# Hbridge0.net
KiCad netlist of a schematic drawn in Altium Designer
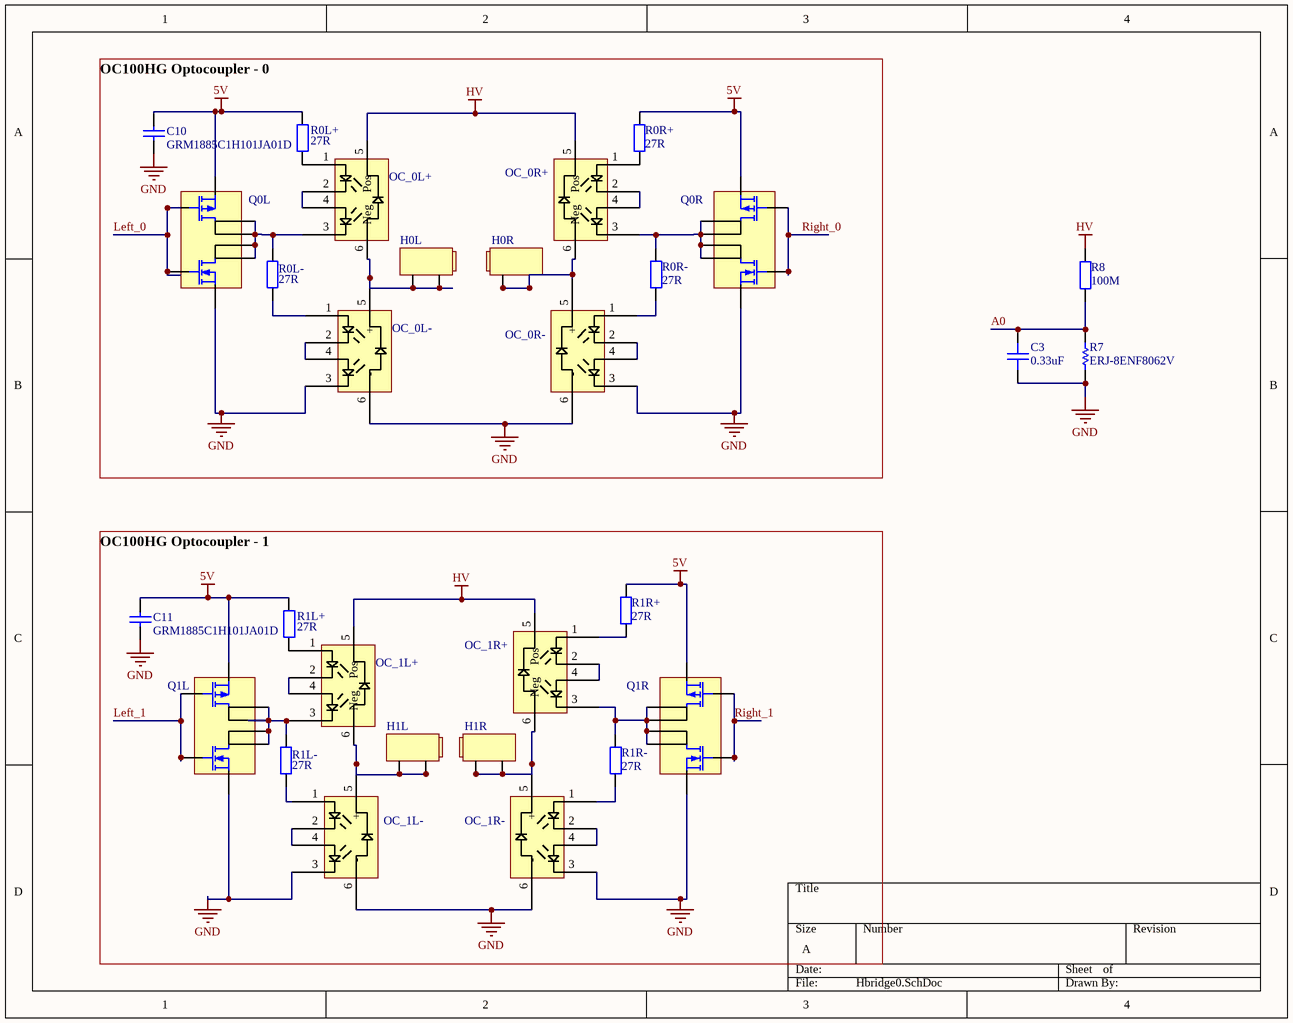
[diagram p0: Hbridge0.SchDoc]

(export (version "E")
  (design (tool "Eeschema 10.0.6"))
  (components
    (comp (ref "C3")
      (value "0.33uF")
      (footprint "1206 CAP")
      (description "‎399-1285-1-ND‎ Manufacturer: ‎C1206C334K3RACTU‎")
      (fields (field (name "Comment") "Capacitor 0.33uF"))
      (libsource (lib "Schlib") (part "Capacitor 0.33uF"))
    )
    (comp (ref "C10")
      (value "GRM1885C1H101JA01D")
      (footprint "CAPC1608X90X35NL10T15")
      (fields (field (name "MANUFACTURER") "Murata"))
      (libsource (lib "Altium Content Vault") (part "CAP"))
    )
    (comp (ref "C11")
      (value "GRM1885C1H101JA01D")
      (footprint "CAPC1608X90X35NL10T15")
      (fields (field (name "MANUFACTURER") "Murata"))
      (libsource (lib "Altium Content Vault") (part "CAP"))
    )
    (comp (ref "H0L")
      (value "HV Socket")
      (footprint "HV Socket 2mm")
      (description "Black: 486-3654-ND\r\nRed: ‎486-3655-ND‎")
      (libsource (lib "") (part "HV Socket_1"))
    )
    (comp (ref "H0R")
      (value "HV Socket")
      (footprint "HV Socket 2mm")
      (description "Black: 486-3654-ND\r\nRed: ‎486-3655-ND‎")
      (libsource (lib "Schlib") (part "HV Socket"))
    )
    (comp (ref "H1L")
      (value "HV Socket")
      (footprint "HV Socket 2mm")
      (description "Black: 486-3654-ND\r\nRed: ‎486-3655-ND‎")
      (libsource (lib "") (part "HV Socket_1"))
    )
    (comp (ref "H1R")
      (value "HV Socket")
      (footprint "HV Socket 2mm")
      (description "Black: 486-3654-ND\r\nRed: ‎486-3655-ND‎")
      (libsource (lib "Schlib") (part "HV Socket"))
    )
    (comp (ref "OC_0L+") (value "OC100HG") (footprint "OC100G") (libsource (lib "") (part "OC100HG_1")))
    (comp (ref "OC_0L-") (value "OC100HG") (footprint "OC100G") (libsource (lib "") (part "OC100HG_3")))
    (comp (ref "OC_0R+") (value "OC100HG") (footprint "OC100G") (libsource (lib "") (part "OC100HG_2")))
    (comp (ref "OC_0R-") (value "OC100HG") (footprint "OC100G") (libsource (lib "Schlib1") (part "OC100HG")))
    (comp (ref "OC_1L+") (value "OC100HG") (footprint "OC100G") (libsource (lib "") (part "OC100HG_1")))
    (comp (ref "OC_1L-") (value "OC100HG") (footprint "OC100G") (libsource (lib "") (part "OC100HG_3")))
    (comp (ref "OC_1R+") (value "OC100HG") (footprint "OC100G") (libsource (lib "") (part "OC100HG_2")))
    (comp (ref "OC_1R-") (value "OC100HG") (footprint "OC100G") (libsource (lib "Schlib1") (part "OC100HG")))
    (comp (ref "Q0L")
      (value "Dual MOSFET")
      (footprint "SO-8")
      (libsource (lib "Schlib") (part "Dual MOSFET"))
    )
    (comp (ref "Q0R") (value "Dual MOSFET") (footprint "SO-8") (libsource (lib "") (part "Dual MOSFET_1")))
    (comp (ref "Q1L")
      (value "Dual MOSFET")
      (footprint "SO-8")
      (libsource (lib "Schlib") (part "Dual MOSFET"))
    )
    (comp (ref "Q1R") (value "Dual MOSFET") (footprint "SO-8") (libsource (lib "") (part "Dual MOSFET_1")))
    (comp (ref "R0L+")
      (value "27R")
      (footprint "1206 R")
      (description "Manufacturer ‎HRG3216Q-27R0-D-T1‎\r\nDigikey ‎408-1908-1-ND")
      (fields (field (name "Comment") "Resistor"))
      (libsource (lib "") (part "Resistor 27R_2"))
    )
    (comp (ref "R0L-")
      (value "27R")
      (footprint "1206 R")
      (description "Manufacturer ‎HRG3216Q-27R0-D-T1‎\r\nDigikey ‎408-1908-1-ND")
      (fields (field (name "Comment") "Resistor"))
      (libsource (lib "") (part "Resistor 27R_1"))
    )
    (comp (ref "R0R+")
      (value "27R")
      (footprint "1206 R")
      (description "Manufacturer ‎HRG3216Q-27R0-D-T1‎\r\nDigikey ‎408-1908-1-ND")
      (fields (field (name "Comment") "Resistor"))
      (libsource (lib "Schlib") (part "Resistor 27R"))
    )
    (comp (ref "R0R-")
      (value "27R")
      (footprint "1206 R")
      (description "Manufacturer ‎HRG3216Q-27R0-D-T1‎\r\nDigikey ‎408-1908-1-ND")
      (fields (field (name "Comment") "Resistor"))
      (libsource (lib "") (part "Resistor 27R_3"))
    )
    (comp (ref "R1L+")
      (value "27R")
      (footprint "1206 R")
      (description "Manufacturer ‎HRG3216Q-27R0-D-T1‎\r\nDigikey ‎408-1908-1-ND")
      (fields (field (name "Comment") "Resistor"))
      (libsource (lib "") (part "Resistor 27R_2"))
    )
    (comp (ref "R1L-")
      (value "27R")
      (footprint "1206 R")
      (description "Manufacturer ‎HRG3216Q-27R0-D-T1‎\r\nDigikey ‎408-1908-1-ND")
      (fields (field (name "Comment") "Resistor"))
      (libsource (lib "") (part "Resistor 27R_1"))
    )
    (comp (ref "R1R+")
      (value "27R")
      (footprint "1206 R")
      (description "Manufacturer ‎HRG3216Q-27R0-D-T1‎\r\nDigikey ‎408-1908-1-ND")
      (fields (field (name "Comment") "Resistor"))
      (libsource (lib "Schlib") (part "Resistor 27R"))
    )
    (comp (ref "R1R-")
      (value "27R")
      (footprint "1206 R")
      (description "Manufacturer ‎HRG3216Q-27R0-D-T1‎\r\nDigikey ‎408-1908-1-ND")
      (fields (field (name "Comment") "Resistor"))
      (libsource (lib "") (part "Resistor 27R_3"))
    )
    (comp (ref "R7")
      (value "ERJ-8ENF8062V")
      (footprint "RESC3216X70X50LL05T20")
      (fields (field (name "MANUFACTURER") "Panasonic"))
      (libsource (lib "Altium Content Vault") (part "RES"))
    )
    (comp (ref "R8")
      (value "100M")
      (footprint "HV resistor")
      (description "Digikey:‎SM102031006FE-ND‎\r\nManufacturer: ‎SM102031006FE-ND‎")
      (fields (field (name "Comment") "Resistor"))
      (libsource (lib "Schlib") (part "Resistor 100M"))
    )
  )
  (nets
    (net (code "1") (name "/A0") (class "Default")
      (node (ref "C3") (pin "2") (pinfunction "2_2") (pintype "passive"))
      (node (ref "R7") (pin "2") (pinfunction "2_2") (pintype "passive"))
      (node (ref "R8") (pin "1") (pinfunction "1_1") (pintype "passive"))
    )
    (net (code "2") (name "/Left_0") (class "Default")
      (node (ref "Q0L") (pin "2") (pinfunction "2_2") (pintype "passive"))
      (node (ref "Q0L") (pin "4") (pinfunction "4_4") (pintype "passive"))
    )
    (net (code "3") (name "/Left_1") (class "Default")
      (node (ref "Q1L") (pin "2") (pinfunction "2_2") (pintype "passive"))
      (node (ref "Q1L") (pin "4") (pinfunction "4_4") (pintype "passive"))
    )
    (net (code "4") (name "/Right_0") (class "Default")
      (node (ref "Q0R") (pin "2") (pinfunction "2_2") (pintype "passive"))
      (node (ref "Q0R") (pin "4") (pinfunction "4_4") (pintype "passive"))
    )
    (net (code "5") (name "/Right_1") (class "Default")
      (node (ref "Q1R") (pin "2") (pinfunction "2_2") (pintype "passive"))
      (node (ref "Q1R") (pin "4") (pinfunction "4_4") (pintype "passive"))
    )
    (net (code "6") (name "5V") (class "Default")
      (node (ref "C10") (pin "2") (pinfunction "2_2") (pintype "passive"))
      (node (ref "C11") (pin "2") (pinfunction "2_2") (pintype "passive"))
      (node (ref "Q0L") (pin "3") (pinfunction "3_3") (pintype "passive"))
      (node (ref "Q0R") (pin "3") (pinfunction "3_3") (pintype "passive"))
      (node (ref "Q1L") (pin "3") (pinfunction "3_3") (pintype "passive"))
      (node (ref "Q1R") (pin "3") (pinfunction "3_3") (pintype "passive"))
      (node (ref "R0L+") (pin "2") (pinfunction "2_2") (pintype "passive"))
      (node (ref "R0R+") (pin "2") (pinfunction "2_2") (pintype "passive"))
      (node (ref "R1L+") (pin "2") (pinfunction "2_2") (pintype "passive"))
      (node (ref "R1R+") (pin "2") (pinfunction "2_2") (pintype "passive"))
    )
    (net (code "7") (name "GND") (class "Default")
      (node (ref "C10") (pin "1") (pinfunction "1_1") (pintype "passive"))
      (node (ref "C11") (pin "1") (pinfunction "1_1") (pintype "passive"))
      (node (ref "C3") (pin "1") (pinfunction "1_1") (pintype "passive"))
      (node (ref "OC_0L-") (pin "3") (pinfunction "LED_2-_3") (pintype "passive"))
      (node (ref "OC_0L-") (pin "6") (pinfunction "-_6") (pintype "passive"))
      (node (ref "OC_0R-") (pin "3") (pinfunction "LED_2-_3") (pintype "passive"))
      (node (ref "OC_0R-") (pin "6") (pinfunction "-_6") (pintype "passive"))
      (node (ref "OC_1L-") (pin "3") (pinfunction "LED_2-_3") (pintype "passive"))
      (node (ref "OC_1L-") (pin "6") (pinfunction "-_6") (pintype "passive"))
      (node (ref "OC_1R-") (pin "3") (pinfunction "LED_2-_3") (pintype "passive"))
      (node (ref "OC_1R-") (pin "6") (pinfunction "-_6") (pintype "passive"))
      (node (ref "Q0L") (pin "1") (pinfunction "1_1") (pintype "passive"))
      (node (ref "Q0R") (pin "1") (pinfunction "1_1") (pintype "passive"))
      (node (ref "Q1L") (pin "1") (pinfunction "1_1") (pintype "passive"))
      (node (ref "Q1R") (pin "1") (pinfunction "1_1") (pintype "passive"))
      (node (ref "R7") (pin "1") (pinfunction "1_1") (pintype "passive"))
    )
    (net (code "8") (name "HV") (class "Default")
      (node (ref "OC_0L+") (pin "5") (pinfunction "Pos_5") (pintype "passive"))
      (node (ref "OC_0R+") (pin "5") (pinfunction "Pos_5") (pintype "passive"))
      (node (ref "OC_1L+") (pin "5") (pinfunction "Pos_5") (pintype "passive"))
      (node (ref "OC_1R+") (pin "5") (pinfunction "Pos_5") (pintype "passive"))
      (node (ref "R8") (pin "2") (pinfunction "2_2") (pintype "passive"))
    )
    (net (code "9") (name "Net-(OC_0L+-LED_1+)") (class "Default")
      (node (ref "OC_0L+") (pin "1") (pinfunction "LED_1+_1") (pintype "passive"))
      (node (ref "R0L+") (pin "1") (pinfunction "1_1") (pintype "passive"))
    )
    (net (code "10") (name "Net-(OC_0L+-LED_1-)") (class "Default")
      (node (ref "OC_0L+") (pin "2") (pinfunction "LED_1-_2") (pintype "passive"))
      (node (ref "OC_0L+") (pin "4") (pinfunction "LED_2+_4") (pintype "passive"))
    )
    (net (code "11") (name "Net-(OC_0L+-LED_2-)") (class "Default")
      (node (ref "OC_0L+") (pin "3") (pinfunction "LED_2-_3") (pintype "passive"))
      (node (ref "Q0L") (pin "5") (pinfunction "5_5") (pintype "passive"))
      (node (ref "Q0L") (pin "6") (pinfunction "6_6") (pintype "passive"))
      (node (ref "Q0L") (pin "7") (pinfunction "7_7") (pintype "passive"))
      (node (ref "Q0L") (pin "8") (pinfunction "8_8") (pintype "passive"))
      (node (ref "R0L-") (pin "1") (pinfunction "1_1") (pintype "passive"))
    )
    (net (code "12") (name "Net-(OC_0L+-Neg)") (class "Default")
      (node (ref "H0L") (pin "1") (pinfunction "1_1") (pintype "passive"))
      (node (ref "H0L") (pin "2") (pinfunction "2_2") (pintype "passive"))
      (node (ref "OC_0L+") (pin "6") (pinfunction "Neg_6") (pintype "passive"))
      (node (ref "OC_0L-") (pin "5") (pinfunction "+_5") (pintype "passive"))
    )
    (net (code "13") (name "Net-(OC_0L--LED_1+)") (class "Default")
      (node (ref "OC_0L-") (pin "1") (pinfunction "LED_1+_1") (pintype "passive"))
      (node (ref "R0L-") (pin "2") (pinfunction "2_2") (pintype "passive"))
    )
    (net (code "14") (name "Net-(OC_0L--LED_1-)") (class "Default")
      (node (ref "OC_0L-") (pin "2") (pinfunction "LED_1-_2") (pintype "passive"))
      (node (ref "OC_0L-") (pin "4") (pinfunction "LED_2+_4") (pintype "passive"))
    )
    (net (code "15") (name "Net-(OC_0R+-LED_1+)") (class "Default")
      (node (ref "OC_0R+") (pin "1") (pinfunction "LED_1+_1") (pintype "passive"))
      (node (ref "R0R+") (pin "1") (pinfunction "1_1") (pintype "passive"))
    )
    (net (code "16") (name "Net-(OC_0R+-LED_1-)") (class "Default")
      (node (ref "OC_0R+") (pin "2") (pinfunction "LED_1-_2") (pintype "passive"))
      (node (ref "OC_0R+") (pin "4") (pinfunction "LED_2+_4") (pintype "passive"))
    )
    (net (code "17") (name "Net-(OC_0R+-LED_2-)") (class "Default")
      (node (ref "OC_0R+") (pin "3") (pinfunction "LED_2-_3") (pintype "passive"))
      (node (ref "Q0R") (pin "5") (pinfunction "5_5") (pintype "passive"))
      (node (ref "Q0R") (pin "6") (pinfunction "6_6") (pintype "passive"))
      (node (ref "Q0R") (pin "7") (pinfunction "7_7") (pintype "passive"))
      (node (ref "Q0R") (pin "8") (pinfunction "8_8") (pintype "passive"))
      (node (ref "R0R-") (pin "1") (pinfunction "1_1") (pintype "passive"))
    )
    (net (code "18") (name "Net-(OC_0R+-Neg)") (class "Default")
      (node (ref "H0R") (pin "1") (pinfunction "1_1") (pintype "passive"))
      (node (ref "H0R") (pin "2") (pinfunction "2_2") (pintype "passive"))
      (node (ref "OC_0R+") (pin "6") (pinfunction "Neg_6") (pintype "passive"))
      (node (ref "OC_0R-") (pin "5") (pinfunction "+_5") (pintype "passive"))
    )
    (net (code "19") (name "Net-(OC_0R--LED_1+)") (class "Default")
      (node (ref "OC_0R-") (pin "1") (pinfunction "LED_1+_1") (pintype "passive"))
      (node (ref "R0R-") (pin "2") (pinfunction "2_2") (pintype "passive"))
    )
    (net (code "20") (name "Net-(OC_0R--LED_1-)") (class "Default")
      (node (ref "OC_0R-") (pin "2") (pinfunction "LED_1-_2") (pintype "passive"))
      (node (ref "OC_0R-") (pin "4") (pinfunction "LED_2+_4") (pintype "passive"))
    )
    (net (code "21") (name "Net-(OC_1L+-LED_1+)") (class "Default")
      (node (ref "OC_1L+") (pin "1") (pinfunction "LED_1+_1") (pintype "passive"))
      (node (ref "R1L+") (pin "1") (pinfunction "1_1") (pintype "passive"))
    )
    (net (code "22") (name "Net-(OC_1L+-LED_1-)") (class "Default")
      (node (ref "OC_1L+") (pin "2") (pinfunction "LED_1-_2") (pintype "passive"))
      (node (ref "OC_1L+") (pin "4") (pinfunction "LED_2+_4") (pintype "passive"))
    )
    (net (code "23") (name "Net-(OC_1L+-LED_2-)") (class "Default")
      (node (ref "OC_1L+") (pin "3") (pinfunction "LED_2-_3") (pintype "passive"))
      (node (ref "Q1L") (pin "5") (pinfunction "5_5") (pintype "passive"))
      (node (ref "Q1L") (pin "6") (pinfunction "6_6") (pintype "passive"))
      (node (ref "Q1L") (pin "7") (pinfunction "7_7") (pintype "passive"))
      (node (ref "Q1L") (pin "8") (pinfunction "8_8") (pintype "passive"))
      (node (ref "R1L-") (pin "1") (pinfunction "1_1") (pintype "passive"))
    )
    (net (code "24") (name "Net-(OC_1L+-Neg)") (class "Default")
      (node (ref "H1L") (pin "1") (pinfunction "1_1") (pintype "passive"))
      (node (ref "H1L") (pin "2") (pinfunction "2_2") (pintype "passive"))
      (node (ref "OC_1L+") (pin "6") (pinfunction "Neg_6") (pintype "passive"))
      (node (ref "OC_1L-") (pin "5") (pinfunction "+_5") (pintype "passive"))
    )
    (net (code "25") (name "Net-(OC_1L--LED_1+)") (class "Default")
      (node (ref "OC_1L-") (pin "1") (pinfunction "LED_1+_1") (pintype "passive"))
      (node (ref "R1L-") (pin "2") (pinfunction "2_2") (pintype "passive"))
    )
    (net (code "26") (name "Net-(OC_1L--LED_1-)") (class "Default")
      (node (ref "OC_1L-") (pin "2") (pinfunction "LED_1-_2") (pintype "passive"))
      (node (ref "OC_1L-") (pin "4") (pinfunction "LED_2+_4") (pintype "passive"))
    )
    (net (code "27") (name "Net-(OC_1R+-LED_1+)") (class "Default")
      (node (ref "OC_1R+") (pin "1") (pinfunction "LED_1+_1") (pintype "passive"))
      (node (ref "R1R+") (pin "1") (pinfunction "1_1") (pintype "passive"))
    )
    (net (code "28") (name "Net-(OC_1R+-LED_1-)") (class "Default")
      (node (ref "OC_1R+") (pin "2") (pinfunction "LED_1-_2") (pintype "passive"))
      (node (ref "OC_1R+") (pin "4") (pinfunction "LED_2+_4") (pintype "passive"))
    )
    (net (code "29") (name "Net-(OC_1R+-LED_2-)") (class "Default")
      (node (ref "OC_1R+") (pin "3") (pinfunction "LED_2-_3") (pintype "passive"))
      (node (ref "Q1R") (pin "5") (pinfunction "5_5") (pintype "passive"))
      (node (ref "Q1R") (pin "6") (pinfunction "6_6") (pintype "passive"))
      (node (ref "Q1R") (pin "7") (pinfunction "7_7") (pintype "passive"))
      (node (ref "Q1R") (pin "8") (pinfunction "8_8") (pintype "passive"))
      (node (ref "R1R-") (pin "1") (pinfunction "1_1") (pintype "passive"))
    )
    (net (code "30") (name "Net-(OC_1R+-Neg)") (class "Default")
      (node (ref "H1R") (pin "1") (pinfunction "1_1") (pintype "passive"))
      (node (ref "H1R") (pin "2") (pinfunction "2_2") (pintype "passive"))
      (node (ref "OC_1R+") (pin "6") (pinfunction "Neg_6") (pintype "passive"))
      (node (ref "OC_1R-") (pin "5") (pinfunction "+_5") (pintype "passive"))
    )
    (net (code "31") (name "Net-(OC_1R--LED_1+)") (class "Default")
      (node (ref "OC_1R-") (pin "1") (pinfunction "LED_1+_1") (pintype "passive"))
      (node (ref "R1R-") (pin "2") (pinfunction "2_2") (pintype "passive"))
    )
    (net (code "32") (name "Net-(OC_1R--LED_1-)") (class "Default")
      (node (ref "OC_1R-") (pin "2") (pinfunction "LED_1-_2") (pintype "passive"))
      (node (ref "OC_1R-") (pin "4") (pinfunction "LED_2+_4") (pintype "passive"))
    )
  )
)
